# curr_sens_sch.net
KiCad netlist of a schematic drawn in Altium Designer
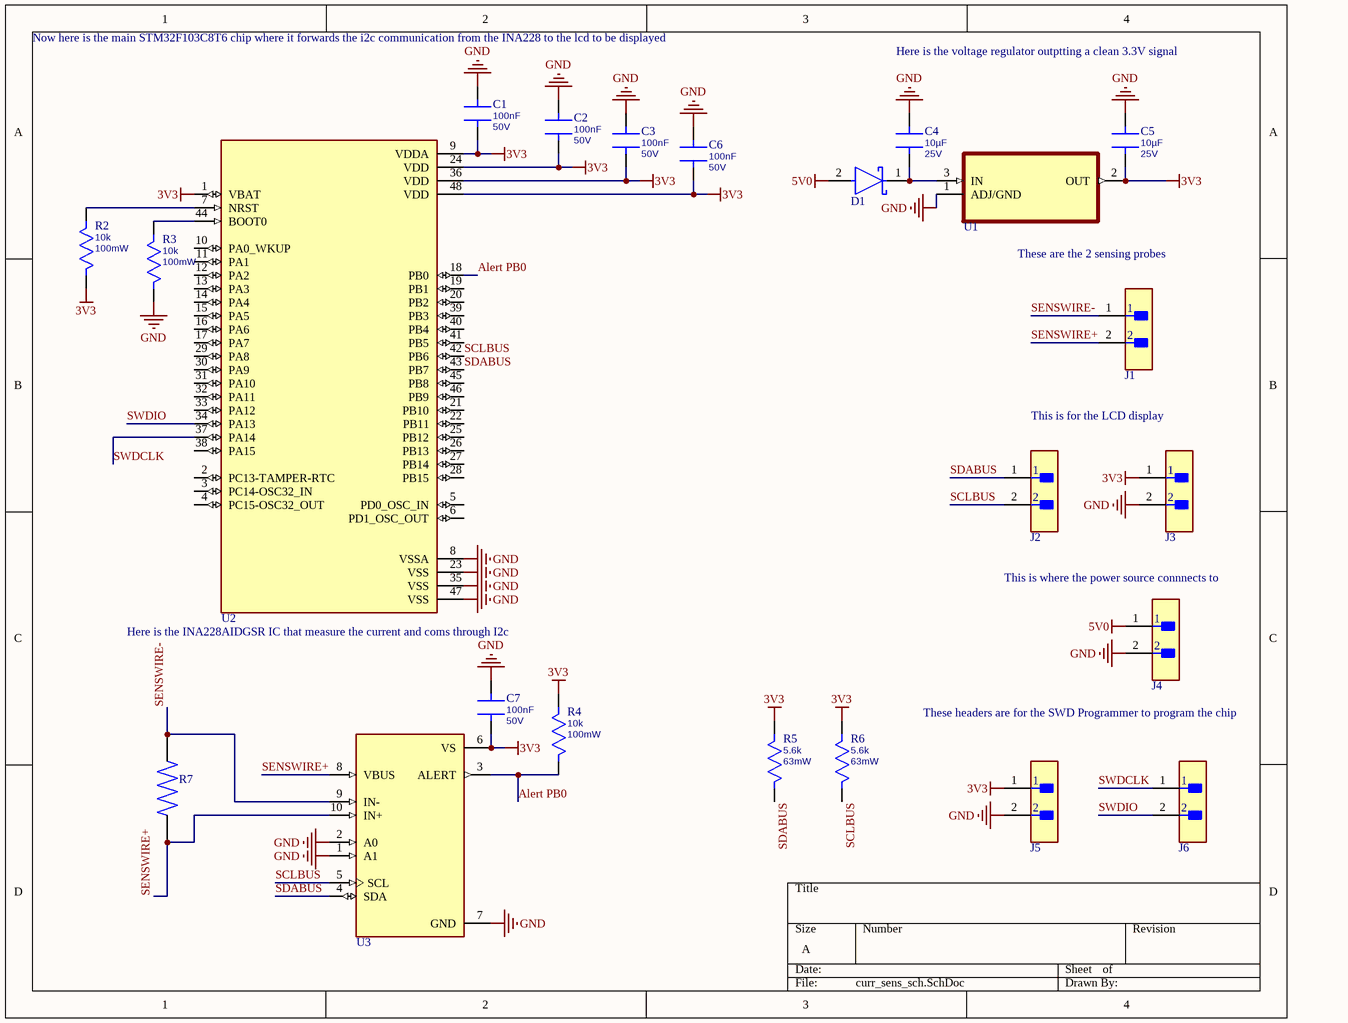
[diagram p0: curr_sens_sch.SchDoc]

(export (version "E")
  (design (tool "Eeschema 10.0.6"))
  (components
    (comp (ref "C1")
      (value "CAP 100nF 50V X7R 10% 0603 CAP")
      (footprint "Standard 0603")
      (description "50V 100nF X7R ±10% 0603 Multilayer Ceramic Capacitors MLCC - SMD/SMT ROHS")
      (fields
        (field (name "CAPACITANCE") "100nF")
        (field (name "VOLTAGE RATING") "50V")
        (field (name "MPN") "CC0603KRX7R9BB104")
        (field (name "JLC PART #") "C14663")
      )
      (libsource (lib "RIT-EVT-Vault") (part "Standard Capacitor"))
    )
    (comp (ref "C2")
      (value "CAP 100nF 50V X7R 10% 0603 CAP")
      (footprint "Standard 0603")
      (description "50V 100nF X7R ±10% 0603 Multilayer Ceramic Capacitors MLCC - SMD/SMT ROHS")
      (fields
        (field (name "CAPACITANCE") "100nF")
        (field (name "VOLTAGE RATING") "50V")
        (field (name "MPN") "CC0603KRX7R9BB104")
        (field (name "JLC PART #") "C14663")
      )
      (libsource (lib "RIT-EVT-Vault") (part "Standard Capacitor"))
    )
    (comp (ref "C3")
      (value "CAP 100nF 50V X7R 10% 0603 CAP")
      (footprint "Standard 0603")
      (description "50V 100nF X7R ±10% 0603 Multilayer Ceramic Capacitors MLCC - SMD/SMT ROHS")
      (fields
        (field (name "CAPACITANCE") "100nF")
        (field (name "VOLTAGE RATING") "50V")
        (field (name "MPN") "CC0603KRX7R9BB104")
        (field (name "JLC PART #") "C14663")
      )
      (libsource (lib "RIT-EVT-Vault") (part "Standard Capacitor"))
    )
    (comp (ref "C4")
      (value "CAP 10u0 25V X5R 10% 0603")
      (footprint "Standard 0603")
      (description "10uF 25V X5R ±10% 0603 Multilayer Ceramic Capacitors MLCC - SMD/SMT ROHS")
      (fields
        (field (name "CAPACITANCE") "10µF")
        (field (name "VOLTAGE RATING") "25V")
        (field (name "JLC PART #") "C344022")
        (field (name "MPN") "GRM188R61E106KA73D")
      )
      (libsource (lib "RIT-EVT-Vault") (part "Standard Capacitor"))
    )
    (comp (ref "C5")
      (value "CAP 10u0 25V X5R 10% 0603")
      (footprint "Standard 0603")
      (description "10uF 25V X5R ±10% 0603 Multilayer Ceramic Capacitors MLCC - SMD/SMT ROHS")
      (fields
        (field (name "CAPACITANCE") "10µF")
        (field (name "VOLTAGE RATING") "25V")
        (field (name "JLC PART #") "C344022")
        (field (name "MPN") "GRM188R61E106KA73D")
      )
      (libsource (lib "RIT-EVT-Vault") (part "Standard Capacitor"))
    )
    (comp (ref "C6")
      (value "CAP 100nF 50V X7R 10% 0603 CAP")
      (footprint "Standard 0603")
      (description "50V 100nF X7R ±10% 0603 Multilayer Ceramic Capacitors MLCC - SMD/SMT ROHS")
      (fields
        (field (name "CAPACITANCE") "100nF")
        (field (name "VOLTAGE RATING") "50V")
        (field (name "MPN") "CC0603KRX7R9BB104")
        (field (name "JLC PART #") "C14663")
      )
      (libsource (lib "RIT-EVT-Vault") (part "Standard Capacitor"))
    )
    (comp (ref "C7")
      (value "CAP 100nF 50V X7R 10% 0603 CAP")
      (footprint "Standard 0603")
      (description "50V 100nF X7R ±10% 0603 Multilayer Ceramic Capacitors MLCC - SMD/SMT ROHS")
      (fields
        (field (name "CAPACITANCE") "100nF")
        (field (name "VOLTAGE RATING") "50V")
        (field (name "MPN") "CC0603KRX7R9BB104")
        (field (name "JLC PART #") "C14663")
      )
      (libsource (lib "RIT-EVT-Vault") (part "Standard Capacitor"))
    )
    (comp (ref "D1")
      (value "MBR0520LT1G")
      (footprint "FP-425-04-IPC_A")
      (description "Diode, Schottky Barrier, Vr 20V, If 0.5A, Pkg SOD-123, Vf 0.385V, Tj +125DEGC, Cs 5.5A")
      (fields (field (name "JLCPCB PART #") "C23848"))
      (libsource (lib "RIT-EVT-Vault") (part "1d6ec82d83fb6aee721767c19dac4b9"))
    )
    (comp (ref "J1")
      (value "TSW-102-07-F-S")
      (footprint "FP-TSW-102-07-F-S-MFG")
      (fields (field (name "JLCPCB PART #") "C3331037"))
      (libsource (lib "RIT-EVT-Vault") (part "3bc925449376181038e59eaffc5286c"))
    )
    (comp (ref "J2")
      (value "TSW-102-07-F-S")
      (footprint "FP-TSW-102-07-F-S-MFG")
      (fields (field (name "JLCPCB PART #") "C3331037"))
      (libsource (lib "RIT-EVT-Vault") (part "3bc925449376181038e59eaffc5286c"))
    )
    (comp (ref "J3")
      (value "TSW-102-07-F-S")
      (footprint "FP-TSW-102-07-F-S-MFG")
      (fields (field (name "JLCPCB PART #") "C3331037"))
      (libsource (lib "RIT-EVT-Vault") (part "3bc925449376181038e59eaffc5286c"))
    )
    (comp (ref "J4")
      (value "TSW-102-07-F-S")
      (footprint "FP-TSW-102-07-F-S-MFG")
      (fields (field (name "JLCPCB PART #") "C3331037"))
      (libsource (lib "RIT-EVT-Vault") (part "3bc925449376181038e59eaffc5286c"))
    )
    (comp (ref "J5")
      (value "TSW-102-07-F-S")
      (footprint "FP-TSW-102-07-F-S-MFG")
      (fields (field (name "JLCPCB PART #") "C3331037"))
      (libsource (lib "RIT-EVT-Vault") (part "3bc925449376181038e59eaffc5286c"))
    )
    (comp (ref "J6")
      (value "TSW-102-07-F-S")
      (footprint "FP-TSW-102-07-F-S-MFG")
      (fields (field (name "JLCPCB PART #") "C3331037"))
      (libsource (lib "RIT-EVT-Vault") (part "3bc925449376181038e59eaffc5286c"))
    )
    (comp (ref "R2")
      (value "RES 10k 100m 0.1% 0603")
      (footprint "Standard 0603")
      (fields
        (field (name "RESISTANCE") "10k")
        (field (name "POWER RATING") "100mW")
        (field (name "TOLERANCE") "0.1%")
        (field (name "JLCPCB PART #") "C95204")
        (field (name "MPN") "RT0603BRD0710KL")
      )
      (libsource (lib "RIT-EVT-Vault") (part "Standard Resistor"))
    )
    (comp (ref "R3")
      (value "RES 10k 100m 0.1% 0603")
      (footprint "Standard 0603")
      (fields
        (field (name "RESISTANCE") "10k")
        (field (name "POWER RATING") "100mW")
        (field (name "TOLERANCE") "0.1%")
        (field (name "JLCPCB PART #") "C95204")
        (field (name "MPN") "RT0603BRD0710KL")
      )
      (libsource (lib "RIT-EVT-Vault") (part "Standard Resistor"))
    )
    (comp (ref "R4")
      (value "RES 10k 100m 0.1% 0603")
      (footprint "Standard 0603")
      (fields
        (field (name "RESISTANCE") "10k")
        (field (name "POWER RATING") "100mW")
        (field (name "TOLERANCE") "0.1%")
        (field (name "JLCPCB PART #") "C95204")
        (field (name "MPN") "RT0603BRD0710KL")
      )
      (libsource (lib "RIT-EVT-Vault") (part "Standard Resistor"))
    )
    (comp (ref "R5")
      (value "RK73B1ETTP562J")
      (footprint "Standard 0402")
      (description "Res Thick Film 0402 5.6K Ohm 5% 0.1W(1/10W) ±200ppm/C Pad SMD Automotive T/R")
      (fields
        (field (name "RESISTANCE") "5.6k")
        (field (name "POWER RATING") "63mW")
        (field (name "JLCPCB PART #") "C131603")
        (field (name "TOLERANCE") "5%")
      )
      (libsource (lib "RIT-EVT-Vault") (part "Standard Resistor"))
    )
    (comp (ref "R6")
      (value "RK73B1ETTP562J")
      (footprint "Standard 0402")
      (description "Res Thick Film 0402 5.6K Ohm 5% 0.1W(1/10W) ±200ppm/C Pad SMD Automotive T/R")
      (fields
        (field (name "RESISTANCE") "5.6k")
        (field (name "POWER RATING") "63mW")
        (field (name "JLCPCB PART #") "C131603")
        (field (name "TOLERANCE") "5%")
      )
      (libsource (lib "RIT-EVT-Vault") (part "Standard Resistor"))
    )
    (comp (ref "R7")
      (value "LTR50UZPF2R20")
      (footprint "RESC2550X65N")
      (fields (field (name "MF") "Rohm"))
      (libsource (lib "LTR50UZPF2R20") (part "LTR50UZPF2R20"))
    )
    (comp (ref "U1")
      (value "LM1117T-3.3")
      (footprint "TO254P470X1016X2222-3P")
      (description "Linear Voltage Regulator IC Positive Fixed 1 Output 800mA TO-220-3")
      (fields (field (name "MF") "Texas Instruments"))
      (libsource (lib "LM1117T-3.3") (part "LM1117T-3.3"))
    )
    (comp (ref "U2")
      (value "STM32F103C8T6")
      (footprint "QFP50P900X900X160-48N")
      (description "ARM® Cortex®-M3 STM32F1 Microcontroller IC 32-Bit 72MHz 64KB (64K x 8) FLASH 48-LQFP (7x7)")
      (fields (field (name "MF") "STMicroelectronics"))
      (libsource (lib "STM32F103C8T6") (part "STM32F103C8T6"))
    )
    (comp (ref "U3")
      (value "INA228AIDGSR")
      (footprint "SOP50P490X110-10N")
      (description "85-V, 20-bit, ultra-precise, I2C output current/voltage/power/energy/charge monitor with alert")
      (fields (field (name "MF") "Texas Instruments"))
      (libsource (lib "INA228AIDGSR") (part "INA228AIDGSR"))
    )
  )
  (nets
    (net (code "1") (name "/Alert PB0") (class "Default")
      (node (ref "R4") (pin "2") (pinfunction "2_2") (pintype "passive"))
      (node (ref "U2") (pin "18") (pinfunction "PB0_18") (pintype "bidirectional"))
      (node (ref "U3") (pin "3") (pinfunction "ALERT_3") (pintype "output"))
    )
    (net (code "2") (name "/SCLBUS") (class "Default")
      (node (ref "J2") (pin "2") (pinfunction "2_2") (pintype "passive"))
      (node (ref "R6") (pin "2") (pinfunction "2_2") (pintype "passive"))
      (node (ref "U2") (pin "42") (pinfunction "PB6_42") (pintype "bidirectional"))
      (node (ref "U3") (pin "5") (pinfunction "SCL_5") (pintype "input"))
    )
    (net (code "3") (name "/SDABUS") (class "Default")
      (node (ref "J2") (pin "1") (pinfunction "1_1") (pintype "passive"))
      (node (ref "R5") (pin "2") (pinfunction "2_2") (pintype "passive"))
      (node (ref "U2") (pin "43") (pinfunction "PB7_43") (pintype "bidirectional"))
      (node (ref "U3") (pin "4") (pinfunction "SDA_4") (pintype "bidirectional"))
    )
    (net (code "4") (name "/SENSWIRE+") (class "Default")
      (node (ref "J1") (pin "2") (pinfunction "2_2") (pintype "passive"))
      (node (ref "R7") (pin "1") (pinfunction "1_1") (pintype "passive"))
      (node (ref "U3") (pin "10") (pinfunction "IN+_10") (pintype "input"))
      (node (ref "U3") (pin "8") (pinfunction "VBUS_8") (pintype "input"))
    )
    (net (code "5") (name "/SENSWIRE-") (class "Default")
      (node (ref "J1") (pin "1") (pinfunction "1_1") (pintype "passive"))
      (node (ref "R7") (pin "2") (pinfunction "2_2") (pintype "passive"))
      (node (ref "U3") (pin "9") (pinfunction "IN-_9") (pintype "input"))
    )
    (net (code "6") (name "/SWDCLK") (class "Default")
      (node (ref "J6") (pin "1") (pinfunction "1_1") (pintype "passive"))
      (node (ref "U2") (pin "37") (pinfunction "PA14_37") (pintype "bidirectional"))
    )
    (net (code "7") (name "/SWDIO") (class "Default")
      (node (ref "J6") (pin "2") (pinfunction "2_2") (pintype "passive"))
      (node (ref "U2") (pin "34") (pinfunction "PA13_34") (pintype "bidirectional"))
    )
    (net (code "8") (name "3V3") (class "Default")
      (node (ref "C1") (pin "1") (pinfunction "1_1") (pintype "passive"))
      (node (ref "C2") (pin "1") (pinfunction "1_1") (pintype "passive"))
      (node (ref "C3") (pin "1") (pinfunction "1_1") (pintype "passive"))
      (node (ref "C5") (pin "2") (pinfunction "2_2") (pintype "passive"))
      (node (ref "C6") (pin "1") (pinfunction "1_1") (pintype "passive"))
      (node (ref "C7") (pin "1") (pinfunction "1_1") (pintype "passive"))
      (node (ref "J3") (pin "1") (pinfunction "1_1") (pintype "passive"))
      (node (ref "J5") (pin "1") (pinfunction "1_1") (pintype "passive"))
      (node (ref "R2") (pin "2") (pinfunction "2_2") (pintype "passive"))
      (node (ref "R4") (pin "1") (pinfunction "1_1") (pintype "passive"))
      (node (ref "R5") (pin "1") (pinfunction "1_1") (pintype "passive"))
      (node (ref "R6") (pin "1") (pinfunction "1_1") (pintype "passive"))
      (node (ref "U1") (pin "2") (pinfunction "OUT_2") (pintype "output"))
      (node (ref "U2") (pin "1") (pinfunction "VBAT_1") (pintype "bidirectional"))
      (node (ref "U2") (pin "24") (pinfunction "VDD_24") (pintype "power_in"))
      (node (ref "U2") (pin "36") (pinfunction "VDD_36") (pintype "power_in"))
      (node (ref "U2") (pin "48") (pinfunction "VDD_48") (pintype "power_in"))
      (node (ref "U2") (pin "9") (pinfunction "VDDA_9") (pintype "power_in"))
      (node (ref "U3") (pin "6") (pinfunction "VS_6") (pintype "power_in"))
    )
    (net (code "9") (name "5V0") (class "Default")
      (node (ref "D1") (pin "2") (pinfunction "A_2") (pintype "passive"))
      (node (ref "J4") (pin "1") (pinfunction "1_1") (pintype "passive"))
    )
    (net (code "10") (name "GND") (class "Default")
      (node (ref "C1") (pin "2") (pinfunction "2_2") (pintype "passive"))
      (node (ref "C2") (pin "2") (pinfunction "2_2") (pintype "passive"))
      (node (ref "C3") (pin "2") (pinfunction "2_2") (pintype "passive"))
      (node (ref "C4") (pin "1") (pinfunction "1_1") (pintype "passive"))
      (node (ref "C5") (pin "1") (pinfunction "1_1") (pintype "passive"))
      (node (ref "C6") (pin "2") (pinfunction "2_2") (pintype "passive"))
      (node (ref "C7") (pin "2") (pinfunction "2_2") (pintype "passive"))
      (node (ref "J3") (pin "2") (pinfunction "2_2") (pintype "passive"))
      (node (ref "J4") (pin "2") (pinfunction "2_2") (pintype "passive"))
      (node (ref "J5") (pin "2") (pinfunction "2_2") (pintype "passive"))
      (node (ref "R3") (pin "2") (pinfunction "2_2") (pintype "passive"))
      (node (ref "U1") (pin "1") (pinfunction "ADJ/GND_1") (pintype "passive"))
      (node (ref "U2") (pin "23") (pinfunction "VSS_23") (pintype "power_in"))
      (node (ref "U2") (pin "35") (pinfunction "VSS_35") (pintype "power_in"))
      (node (ref "U2") (pin "47") (pinfunction "VSS_47") (pintype "power_in"))
      (node (ref "U2") (pin "8") (pinfunction "VSSA_8") (pintype "power_in"))
      (node (ref "U3") (pin "1") (pinfunction "A1_1") (pintype "input"))
      (node (ref "U3") (pin "2") (pinfunction "A0_2") (pintype "input"))
      (node (ref "U3") (pin "7") (pinfunction "GND_7") (pintype "power_in"))
    )
    (net (code "11") (name "Net-(D1-C)") (class "Default")
      (node (ref "C4") (pin "2") (pinfunction "2_2") (pintype "passive"))
      (node (ref "D1") (pin "1") (pinfunction "C_1") (pintype "passive"))
      (node (ref "U1") (pin "3") (pinfunction "IN_3") (pintype "input"))
    )
    (net (code "12") (name "Net-(U2-BOOT0)") (class "Default")
      (node (ref "R3") (pin "1") (pinfunction "1_1") (pintype "passive"))
      (node (ref "U2") (pin "44") (pinfunction "BOOT0_44") (pintype "input"))
    )
    (net (code "13") (name "Net-(U2-NRST)") (class "Default")
      (node (ref "R2") (pin "1") (pinfunction "1_1") (pintype "passive"))
      (node (ref "U2") (pin "7") (pinfunction "NRST_7") (pintype "input"))
    )
    (net (code "14") (name "unconnected-(U2-PA0_WKUP-Pad10)") (class "Default")
      (node (ref "U2") (pin "10") (pinfunction "PA0_WKUP_10") (pintype "bidirectional"))
    )
    (net (code "15") (name "unconnected-(U2-PA1-Pad11)") (class "Default")
      (node (ref "U2") (pin "11") (pinfunction "PA1_11") (pintype "bidirectional"))
    )
    (net (code "16") (name "unconnected-(U2-PA2-Pad12)") (class "Default")
      (node (ref "U2") (pin "12") (pinfunction "PA2_12") (pintype "bidirectional"))
    )
    (net (code "17") (name "unconnected-(U2-PA3-Pad13)") (class "Default")
      (node (ref "U2") (pin "13") (pinfunction "PA3_13") (pintype "bidirectional"))
    )
    (net (code "18") (name "unconnected-(U2-PA4-Pad14)") (class "Default")
      (node (ref "U2") (pin "14") (pinfunction "PA4_14") (pintype "bidirectional"))
    )
    (net (code "19") (name "unconnected-(U2-PA5-Pad15)") (class "Default")
      (node (ref "U2") (pin "15") (pinfunction "PA5_15") (pintype "bidirectional"))
    )
    (net (code "20") (name "unconnected-(U2-PA6-Pad16)") (class "Default")
      (node (ref "U2") (pin "16") (pinfunction "PA6_16") (pintype "bidirectional"))
    )
    (net (code "21") (name "unconnected-(U2-PA7-Pad17)") (class "Default")
      (node (ref "U2") (pin "17") (pinfunction "PA7_17") (pintype "bidirectional"))
    )
    (net (code "22") (name "unconnected-(U2-PA8-Pad29)") (class "Default")
      (node (ref "U2") (pin "29") (pinfunction "PA8_29") (pintype "bidirectional"))
    )
    (net (code "23") (name "unconnected-(U2-PA9-Pad30)") (class "Default")
      (node (ref "U2") (pin "30") (pinfunction "PA9_30") (pintype "bidirectional"))
    )
    (net (code "24") (name "unconnected-(U2-PA10-Pad31)") (class "Default")
      (node (ref "U2") (pin "31") (pinfunction "PA10_31") (pintype "bidirectional"))
    )
    (net (code "25") (name "unconnected-(U2-PA11-Pad32)") (class "Default")
      (node (ref "U2") (pin "32") (pinfunction "PA11_32") (pintype "bidirectional"))
    )
    (net (code "26") (name "unconnected-(U2-PA12-Pad33)") (class "Default")
      (node (ref "U2") (pin "33") (pinfunction "PA12_33") (pintype "bidirectional"))
    )
    (net (code "27") (name "unconnected-(U2-PA15-Pad38)") (class "Default")
      (node (ref "U2") (pin "38") (pinfunction "PA15_38") (pintype "bidirectional"))
    )
    (net (code "28") (name "unconnected-(U2-PB1-Pad19)") (class "Default")
      (node (ref "U2") (pin "19") (pinfunction "PB1_19") (pintype "bidirectional"))
    )
    (net (code "29") (name "unconnected-(U2-PB2-Pad20)") (class "Default")
      (node (ref "U2") (pin "20") (pinfunction "PB2_20") (pintype "bidirectional"))
    )
    (net (code "30") (name "unconnected-(U2-PB3-Pad39)") (class "Default")
      (node (ref "U2") (pin "39") (pinfunction "PB3_39") (pintype "bidirectional"))
    )
    (net (code "31") (name "unconnected-(U2-PB4-Pad40)") (class "Default")
      (node (ref "U2") (pin "40") (pinfunction "PB4_40") (pintype "bidirectional"))
    )
    (net (code "32") (name "unconnected-(U2-PB5-Pad41)") (class "Default")
      (node (ref "U2") (pin "41") (pinfunction "PB5_41") (pintype "bidirectional"))
    )
    (net (code "33") (name "unconnected-(U2-PB8-Pad45)") (class "Default")
      (node (ref "U2") (pin "45") (pinfunction "PB8_45") (pintype "bidirectional"))
    )
    (net (code "34") (name "unconnected-(U2-PB9-Pad46)") (class "Default")
      (node (ref "U2") (pin "46") (pinfunction "PB9_46") (pintype "bidirectional"))
    )
    (net (code "35") (name "unconnected-(U2-PB10-Pad21)") (class "Default")
      (node (ref "U2") (pin "21") (pinfunction "PB10_21") (pintype "bidirectional"))
    )
    (net (code "36") (name "unconnected-(U2-PB11-Pad22)") (class "Default")
      (node (ref "U2") (pin "22") (pinfunction "PB11_22") (pintype "bidirectional"))
    )
    (net (code "37") (name "unconnected-(U2-PB12-Pad25)") (class "Default")
      (node (ref "U2") (pin "25") (pinfunction "PB12_25") (pintype "bidirectional"))
    )
    (net (code "38") (name "unconnected-(U2-PB13-Pad26)") (class "Default")
      (node (ref "U2") (pin "26") (pinfunction "PB13_26") (pintype "bidirectional"))
    )
    (net (code "39") (name "unconnected-(U2-PB14-Pad27)") (class "Default")
      (node (ref "U2") (pin "27") (pinfunction "PB14_27") (pintype "bidirectional"))
    )
    (net (code "40") (name "unconnected-(U2-PB15-Pad28)") (class "Default")
      (node (ref "U2") (pin "28") (pinfunction "PB15_28") (pintype "bidirectional"))
    )
    (net (code "41") (name "unconnected-(U2-PC13-TAMPER-RTC-Pad2)") (class "Default")
      (node (ref "U2") (pin "2") (pinfunction "PC13-TAMPER-RTC_2") (pintype "bidirectional"))
    )
    (net (code "42") (name "unconnected-(U2-PC14-OSC32_IN-Pad3)") (class "Default")
      (node (ref "U2") (pin "3") (pinfunction "PC14-OSC32_IN_3") (pintype "bidirectional"))
    )
    (net (code "43") (name "unconnected-(U2-PC15-OSC32_OUT-Pad4)") (class "Default")
      (node (ref "U2") (pin "4") (pinfunction "PC15-OSC32_OUT_4") (pintype "bidirectional"))
    )
    (net (code "44") (name "unconnected-(U2-PD0_OSC_IN-Pad5)") (class "Default")
      (node (ref "U2") (pin "5") (pinfunction "PD0_OSC_IN_5") (pintype "bidirectional"))
    )
    (net (code "45") (name "unconnected-(U2-PD1_OSC_OUT-Pad6)") (class "Default")
      (node (ref "U2") (pin "6") (pinfunction "PD1_OSC_OUT_6") (pintype "bidirectional"))
    )
  )
)
